# MCU.net
KiCad netlist of a schematic drawn in Altium Designer
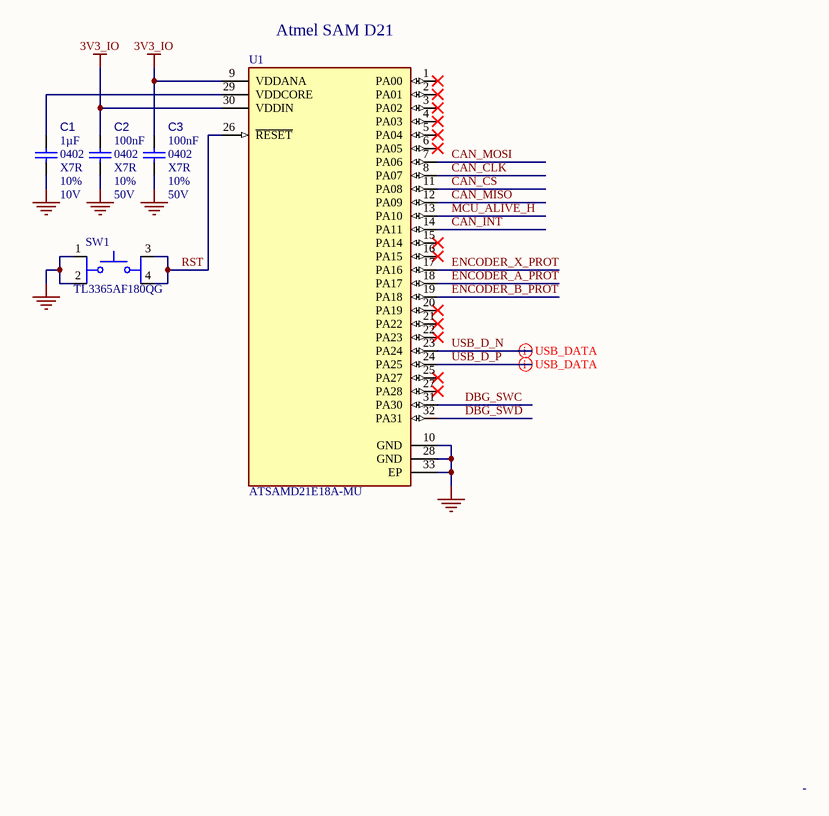
[diagram p0: MCU.SchDoc]

(export (version "E")
  (design (tool "Eeschema 10.0.6"))
  (components
    (comp (ref "C1")
      (value "1µF")
      (footprint "CAPC1005X55X30NL05T10")
      (fields
        (field (name "CASE/PACKAGE") "0402")
        (field (name "VOLTAGE RATING") "10V")
        (field (name "CAPACITOR TYPE") "X7R")
        (field (name "TOLERANCE") "10%")
        (field (name "Comment") "GRM155Z71A105KE01D")
      )
      (libsource (lib "Personal Workspace") (part "CAP-NP-2"))
    )
    (comp (ref "C2")
      (value "100nF")
      (footprint "CAPC1005X55X30NL05T10")
      (fields
        (field (name "VOLTAGE RATING") "50V")
        (field (name "CAPACITOR TYPE") "X7R")
        (field (name "CASE/PACKAGE") "0402")
        (field (name "TOLERANCE") "10%")
        (field (name "Comment") "04025C104KAT4A")
      )
      (libsource (lib "Personal Workspace") (part "CAP-NP-2"))
    )
    (comp (ref "C3")
      (value "100nF")
      (footprint "CAPC1005X55X30NL05T10")
      (fields
        (field (name "VOLTAGE RATING") "50V")
        (field (name "CAPACITOR TYPE") "X7R")
        (field (name "CASE/PACKAGE") "0402")
        (field (name "TOLERANCE") "10%")
        (field (name "Comment") "04025C104KAT4A")
      )
      (libsource (lib "Personal Workspace") (part "CAP-NP-2"))
    )
    (comp (ref "SW1")
      (value "TL3365AF180QG")
      (footprint "SW_TL3365AF180QG")
      (description "Tactile Switch SPST-NO Top Actuated Surface Mount")
      (fields (field (name "MF") "E-Switch"))
      (libsource (lib "Personal Workspace") (part "TL3365AF180QG"))
    )
    (comp (ref "U1")
      (value "ATSAMD21E18A-MU")
      (footprint "FP-PG-IPC_A")
      (description "RISC Microcontroller, 32-Bit, FLASH, CORTEX-M0 CPU, 48MHz, CMOS")
      (libsource (lib "Personal Workspace") (part "079772c84f40789a0aafecd75ebb365"))
    )
  )
  (nets
    (net (code "1") (name "/CAN_CLK") (class "Default")
      (node (ref "U1") (pin "8") (pinfunction "PA07_8") (pintype "bidirectional"))
    )
    (net (code "2") (name "/CAN_CS") (class "Default")
      (node (ref "U1") (pin "11") (pinfunction "PA08_11") (pintype "bidirectional"))
    )
    (net (code "3") (name "/CAN_INT") (class "Default")
      (node (ref "U1") (pin "14") (pinfunction "PA11_14") (pintype "bidirectional"))
    )
    (net (code "4") (name "/CAN_MISO") (class "Default")
      (node (ref "U1") (pin "12") (pinfunction "PA09_12") (pintype "bidirectional"))
    )
    (net (code "5") (name "/CAN_MOSI") (class "Default")
      (node (ref "U1") (pin "7") (pinfunction "PA06_7") (pintype "bidirectional"))
    )
    (net (code "6") (name "/DBG_SWC") (class "Default")
      (node (ref "U1") (pin "31") (pinfunction "PA30_31") (pintype "bidirectional"))
    )
    (net (code "7") (name "/DBG_SWD") (class "Default")
      (node (ref "U1") (pin "32") (pinfunction "PA31_32") (pintype "bidirectional"))
    )
    (net (code "8") (name "/ENCODER_A_PROT") (class "Default")
      (node (ref "U1") (pin "18") (pinfunction "PA17_18") (pintype "bidirectional"))
    )
    (net (code "9") (name "/ENCODER_B_PROT") (class "Default")
      (node (ref "U1") (pin "19") (pinfunction "PA18_19") (pintype "bidirectional"))
    )
    (net (code "10") (name "/ENCODER_X_PROT") (class "Default")
      (node (ref "U1") (pin "17") (pinfunction "PA16_17") (pintype "bidirectional"))
    )
    (net (code "11") (name "/MCU_ALIVE_H") (class "Default")
      (node (ref "U1") (pin "13") (pinfunction "PA10_13") (pintype "bidirectional"))
    )
    (net (code "12") (name "/RST") (class "Default")
      (node (ref "SW1") (pin "3") (pinfunction "3_3") (pintype "passive"))
      (node (ref "SW1") (pin "4") (pinfunction "4_4") (pintype "passive"))
      (node (ref "U1") (pin "26") (pinfunction "~{RESET}_26") (pintype "input"))
    )
    (net (code "13") (name "/USB_D_N") (class "Default")
      (node (ref "U1") (pin "23") (pinfunction "PA24_23") (pintype "bidirectional"))
    )
    (net (code "14") (name "/USB_D_P") (class "Default")
      (node (ref "U1") (pin "24") (pinfunction "PA25_24") (pintype "bidirectional"))
    )
    (net (code "15") (name "3V3_IO") (class "Default")
      (node (ref "C2") (pin "1") (pinfunction "1_1") (pintype "passive"))
      (node (ref "C3") (pin "1") (pinfunction "1_1") (pintype "passive"))
      (node (ref "U1") (pin "30") (pinfunction "VDDIN_30") (pintype "power_in"))
      (node (ref "U1") (pin "9") (pinfunction "VDDANA_9") (pintype "power_in"))
    )
    (net (code "16") (name "GND") (class "Default")
      (node (ref "C1") (pin "2") (pinfunction "2_2") (pintype "passive"))
      (node (ref "C2") (pin "2") (pinfunction "2_2") (pintype "passive"))
      (node (ref "C3") (pin "2") (pinfunction "2_2") (pintype "passive"))
      (node (ref "SW1") (pin "1") (pinfunction "1_1") (pintype "passive"))
      (node (ref "SW1") (pin "2") (pinfunction "2_2") (pintype "passive"))
      (node (ref "U1") (pin "10") (pinfunction "GND_10") (pintype "power_in"))
      (node (ref "U1") (pin "28") (pinfunction "GND_28") (pintype "power_in"))
      (node (ref "U1") (pin "33") (pinfunction "EP_33") (pintype "power_in"))
    )
    (net (code "17") (name "Net-(U1-VDDCORE)") (class "Default")
      (node (ref "C1") (pin "1") (pinfunction "1_1") (pintype "passive"))
      (node (ref "U1") (pin "29") (pinfunction "VDDCORE_29") (pintype "power_in"))
    )
    (net (code "18") (name "unconnected-(U1-PA00-Pad1)") (class "Default")
      (node (ref "U1") (pin "1") (pinfunction "PA00_1") (pintype "bidirectional+no_connect"))
    )
    (net (code "19") (name "unconnected-(U1-PA01-Pad2)") (class "Default")
      (node (ref "U1") (pin "2") (pinfunction "PA01_2") (pintype "bidirectional+no_connect"))
    )
    (net (code "20") (name "unconnected-(U1-PA02-Pad3)") (class "Default")
      (node (ref "U1") (pin "3") (pinfunction "PA02_3") (pintype "bidirectional+no_connect"))
    )
    (net (code "21") (name "unconnected-(U1-PA03-Pad4)") (class "Default")
      (node (ref "U1") (pin "4") (pinfunction "PA03_4") (pintype "bidirectional+no_connect"))
    )
    (net (code "22") (name "unconnected-(U1-PA04-Pad5)") (class "Default")
      (node (ref "U1") (pin "5") (pinfunction "PA04_5") (pintype "bidirectional+no_connect"))
    )
    (net (code "23") (name "unconnected-(U1-PA05-Pad6)") (class "Default")
      (node (ref "U1") (pin "6") (pinfunction "PA05_6") (pintype "bidirectional+no_connect"))
    )
    (net (code "24") (name "unconnected-(U1-PA14-Pad15)") (class "Default")
      (node (ref "U1") (pin "15") (pinfunction "PA14_15") (pintype "bidirectional+no_connect"))
    )
    (net (code "25") (name "unconnected-(U1-PA15-Pad16)") (class "Default")
      (node (ref "U1") (pin "16") (pinfunction "PA15_16") (pintype "bidirectional+no_connect"))
    )
    (net (code "26") (name "unconnected-(U1-PA19-Pad20)") (class "Default")
      (node (ref "U1") (pin "20") (pinfunction "PA19_20") (pintype "bidirectional+no_connect"))
    )
    (net (code "27") (name "unconnected-(U1-PA22-Pad21)") (class "Default")
      (node (ref "U1") (pin "21") (pinfunction "PA22_21") (pintype "bidirectional+no_connect"))
    )
    (net (code "28") (name "unconnected-(U1-PA23-Pad22)") (class "Default")
      (node (ref "U1") (pin "22") (pinfunction "PA23_22") (pintype "bidirectional+no_connect"))
    )
    (net (code "29") (name "unconnected-(U1-PA27-Pad25)") (class "Default")
      (node (ref "U1") (pin "25") (pinfunction "PA27_25") (pintype "bidirectional+no_connect"))
    )
    (net (code "30") (name "unconnected-(U1-PA28-Pad27)") (class "Default")
      (node (ref "U1") (pin "27") (pinfunction "PA28_27") (pintype "bidirectional+no_connect"))
    )
  )
)
